# SCH_SlimeVR_Charge_HUB_2022-04-14.net
KiCad netlist of a schematic drawn in EasyEDA
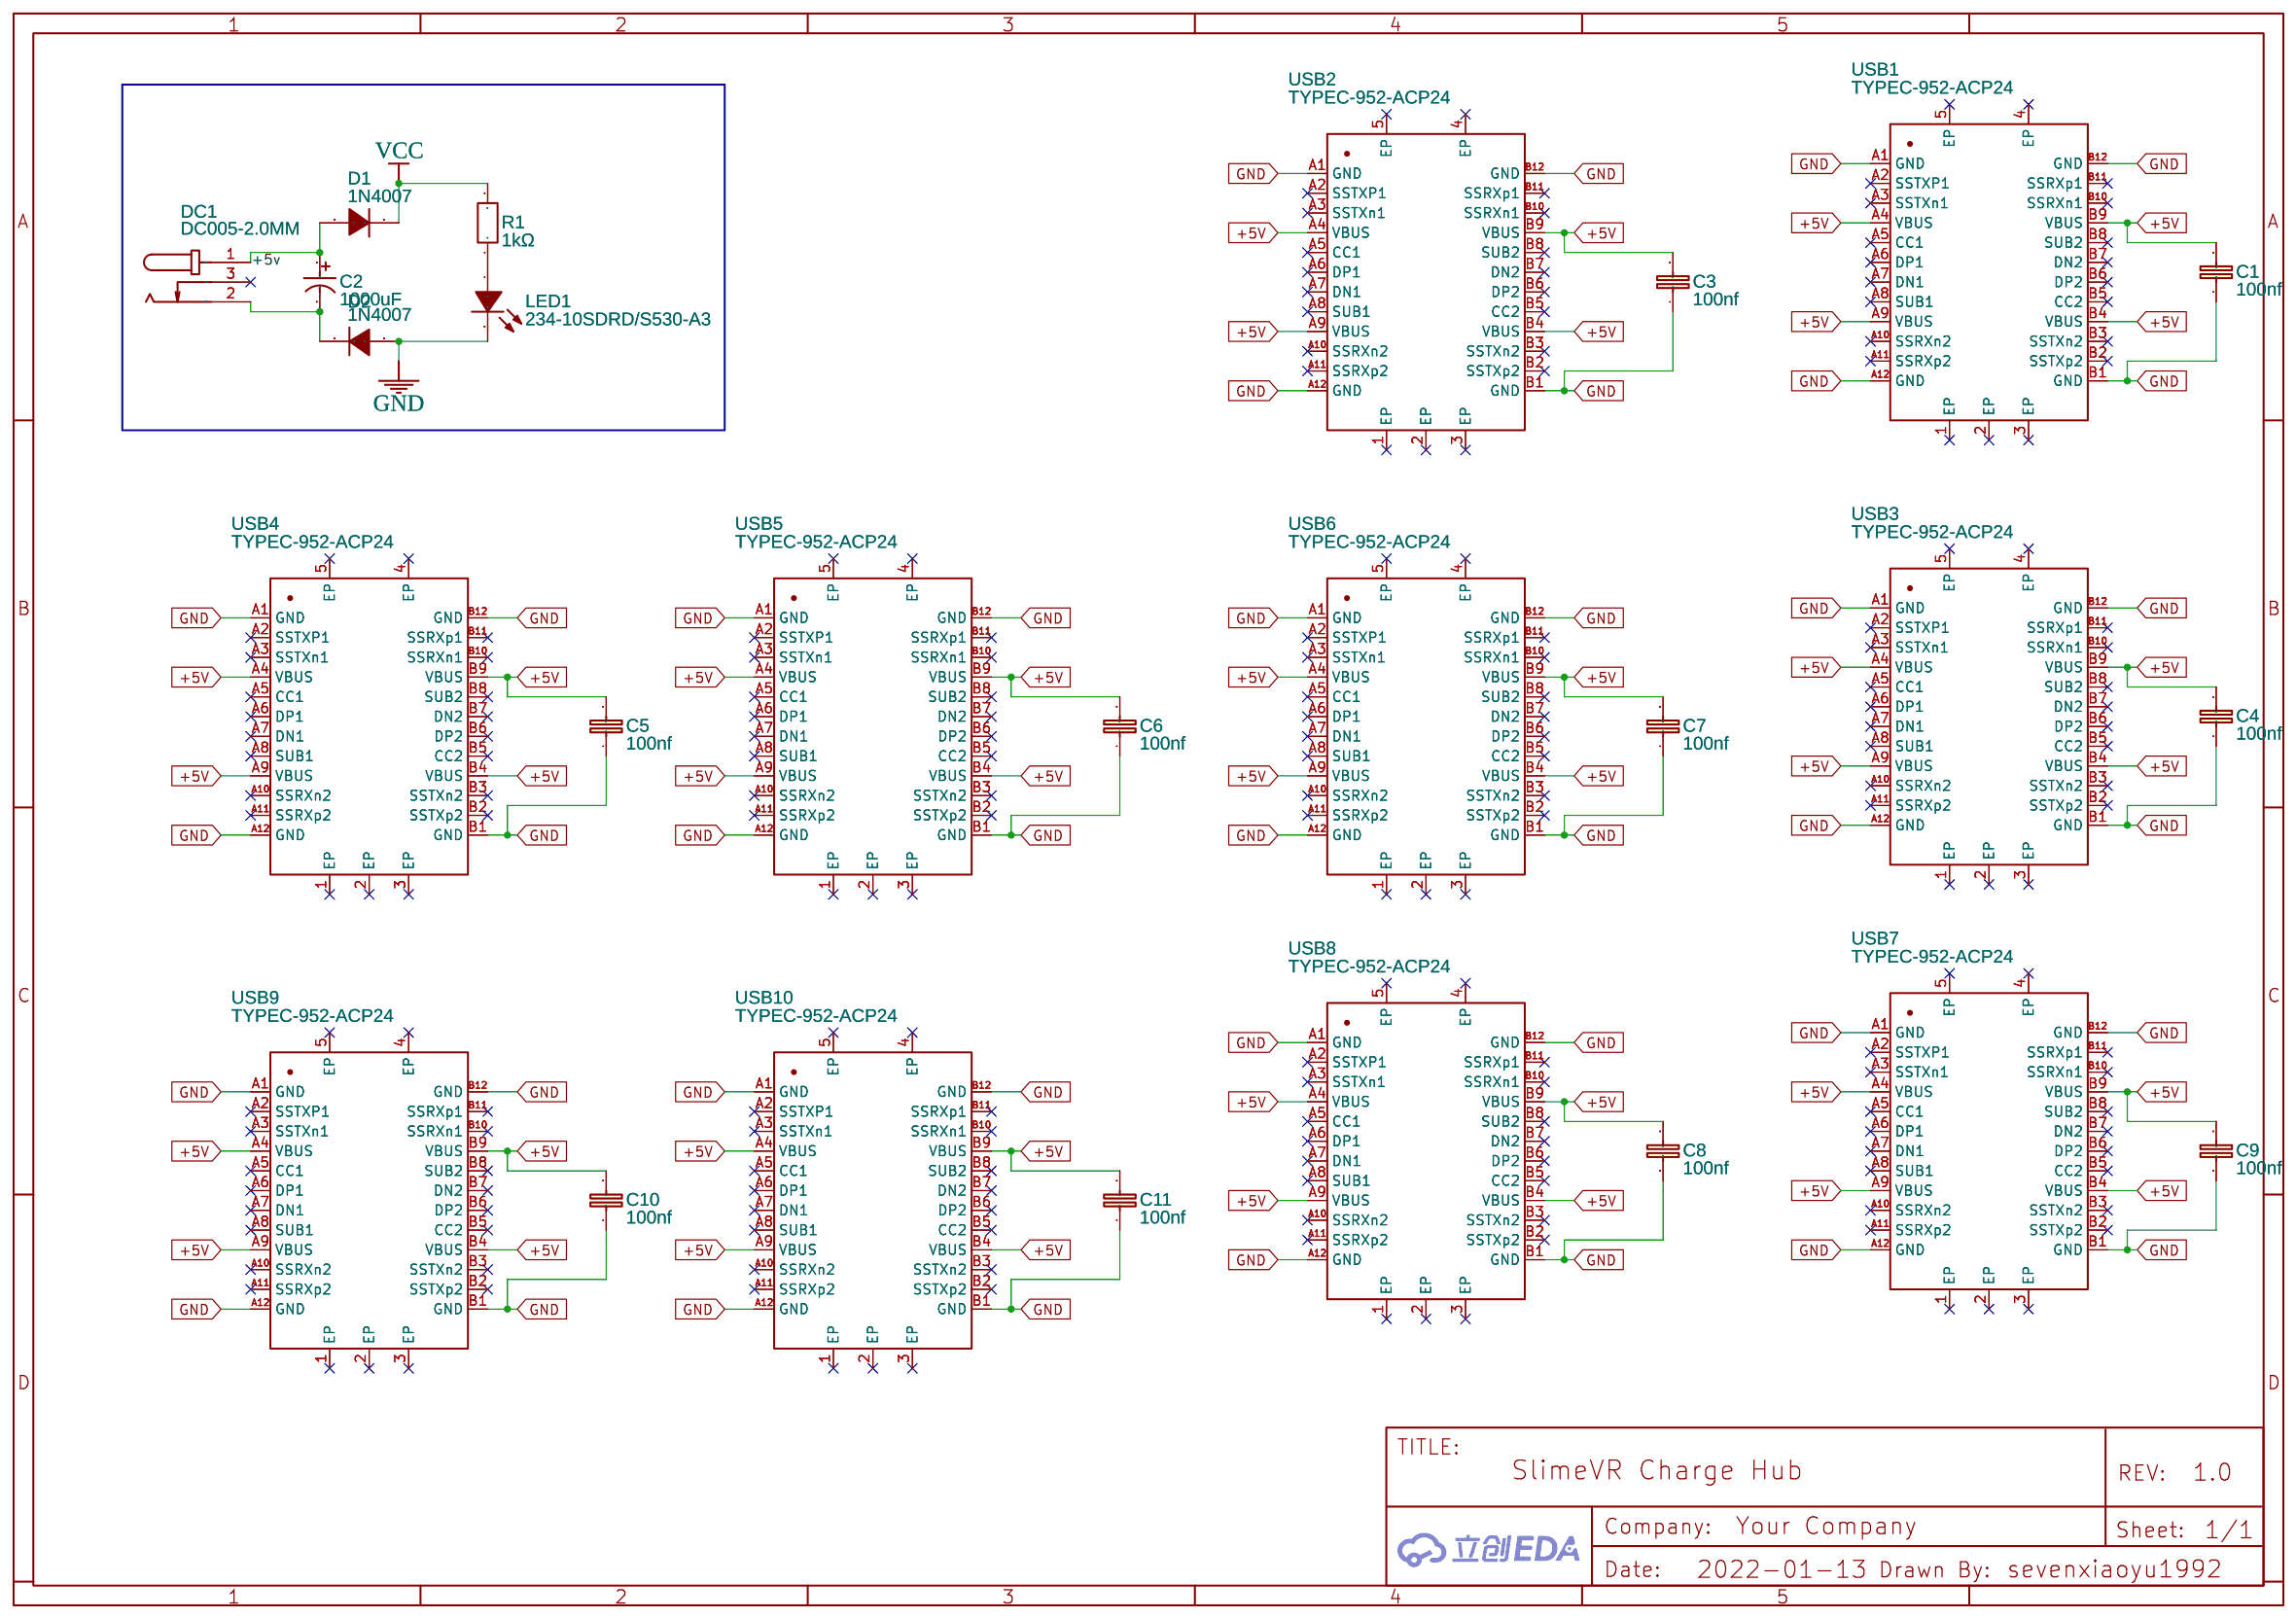
[diagram p0: schematic sheet]

(export (version "E")
  (design (tool "Eeschema 10.0.6"))
  (components
    (comp (ref "C1")
      (value "100nf")
      (fields (field (name "BOM_Manufacturer Part") "?"))
      (libsource (lib "") (part "Unknown_1115_-675"))
    )
    (comp (ref "C2")
      (value "1000uF")
      (fields
        (field (name "BOM_Manufacturer Part") "1000uF 10V绿金 10*15")
        (field (name "BOM_Supplier Part") "C43339")
      )
      (libsource (lib "") (part "1000uF 10V 10*15"))
    )
    (comp (ref "C3")
      (value "100nf")
      (fields (field (name "BOM_Manufacturer Part") "?"))
      (libsource (lib "") (part "Unknown_840_-670"))
    )
    (comp (ref "C4")
      (value "100nf")
      (fields (field (name "BOM_Manufacturer Part") "?"))
      (libsource (lib "") (part "Unknown_1115_-450"))
    )
    (comp (ref "C5")
      (value "100nf")
      (fields (field (name "BOM_Manufacturer Part") "?"))
      (libsource (lib "") (part "Unknown_300_-445"))
    )
    (comp (ref "C6")
      (value "100nf")
      (fields (field (name "BOM_Manufacturer Part") "?"))
      (libsource (lib "") (part "Unknown_560_-445"))
    )
    (comp (ref "C7")
      (value "100nf")
      (fields (field (name "BOM_Manufacturer Part") "?"))
      (libsource (lib "") (part "Unknown_835_-445"))
    )
    (comp (ref "C8")
      (value "100nf")
      (fields (field (name "BOM_Manufacturer Part") "?"))
      (libsource (lib "") (part "Unknown_835_-230"))
    )
    (comp (ref "C9")
      (value "100nf")
      (fields (field (name "BOM_Manufacturer Part") "?"))
      (libsource (lib "") (part "Unknown_1115_-230"))
    )
    (comp (ref "C10")
      (value "100nf")
      (fields (field (name "BOM_Manufacturer Part") "?"))
      (libsource (lib "") (part "Unknown_300_-205"))
    )
    (comp (ref "C11")
      (value "100nf")
      (fields (field (name "BOM_Manufacturer Part") "?"))
      (libsource (lib "") (part "Unknown_560_-205"))
    )
    (comp (ref "D1")
      (value "1N4007")
      (fields (field (name "BOM_Supplier Part") "C106903"))
      (libsource (lib "") (part "1N4007"))
    )
    (comp (ref "D2")
      (value "1N4007")
      (fields (field (name "BOM_Supplier Part") "C106903"))
      (libsource (lib "") (part "1N4007_1"))
    )
    (comp (ref "DC1")
      (value "DC005-2.0MM")
      (fields (field (name "BOM_Supplier Part") "C111567"))
      (libsource (lib "") (part "DC005-2.0MM"))
    )
    (comp (ref "LED1")
      (value "234-10SDRD/S530-A3")
      (fields (field (name "BOM_Supplier Part") "C181866"))
      (libsource (lib "") (part "234-10SDRD/S530-A3"))
    )
    (comp (ref "R1")
      (value "1kΩ")
      (fields
        (field (name "BOM_Manufacturer Part") "MF1/2W-1KΩ±1%T52")
        (field (name "BOM_Supplier Part") "C714068")
      )
      (libsource (lib "") (part "MF1/2W-1KΩ±1%T52"))
    )
    (comp (ref "USB1")
      (value "TYPEC-952-ACP24")
      (fields (field (name "BOM_Supplier Part") "C2840398"))
      (libsource (lib "") (part "TYPEC-952-ACP24"))
    )
    (comp (ref "USB2")
      (value "TYPEC-952-ACP24")
      (fields (field (name "BOM_Supplier Part") "C2840398"))
      (libsource (lib "") (part "TYPEC-952-ACP24"))
    )
    (comp (ref "USB3")
      (value "TYPEC-952-ACP24")
      (fields (field (name "BOM_Supplier Part") "C2840398"))
      (libsource (lib "") (part "TYPEC-952-ACP24"))
    )
    (comp (ref "USB4")
      (value "TYPEC-952-ACP24")
      (fields (field (name "BOM_Supplier Part") "C2840398"))
      (libsource (lib "") (part "TYPEC-952-ACP24"))
    )
    (comp (ref "USB5")
      (value "TYPEC-952-ACP24")
      (fields (field (name "BOM_Supplier Part") "C2840398"))
      (libsource (lib "") (part "TYPEC-952-ACP24"))
    )
    (comp (ref "USB6")
      (value "TYPEC-952-ACP24")
      (fields (field (name "BOM_Supplier Part") "C2840398"))
      (libsource (lib "") (part "TYPEC-952-ACP24"))
    )
    (comp (ref "USB7")
      (value "TYPEC-952-ACP24")
      (fields (field (name "BOM_Supplier Part") "C2840398"))
      (libsource (lib "") (part "TYPEC-952-ACP24"))
    )
    (comp (ref "USB8")
      (value "TYPEC-952-ACP24")
      (fields (field (name "BOM_Supplier Part") "C2840398"))
      (libsource (lib "") (part "TYPEC-952-ACP24"))
    )
    (comp (ref "USB9")
      (value "TYPEC-952-ACP24")
      (fields (field (name "BOM_Supplier Part") "C2840398"))
      (libsource (lib "") (part "TYPEC-952-ACP24"))
    )
    (comp (ref "USB10")
      (value "TYPEC-952-ACP24")
      (fields (field (name "BOM_Supplier Part") "C2840398"))
      (libsource (lib "") (part "TYPEC-952-ACP24"))
    )
  )
  (nets
    (net (code "1") (name "+5V") (class "Default")
      (node (ref "C1") (pin "2") (pinfunction "2_2") (pintype "unspecified"))
      (node (ref "C10") (pin "2") (pinfunction "2_2") (pintype "unspecified"))
      (node (ref "C11") (pin "2") (pinfunction "2_2") (pintype "unspecified"))
      (node (ref "C3") (pin "2") (pinfunction "2_2") (pintype "unspecified"))
      (node (ref "C4") (pin "2") (pinfunction "2_2") (pintype "unspecified"))
      (node (ref "C5") (pin "2") (pinfunction "2_2") (pintype "unspecified"))
      (node (ref "C6") (pin "2") (pinfunction "2_2") (pintype "unspecified"))
      (node (ref "C7") (pin "2") (pinfunction "2_2") (pintype "unspecified"))
      (node (ref "C8") (pin "2") (pinfunction "2_2") (pintype "unspecified"))
      (node (ref "C9") (pin "2") (pinfunction "2_2") (pintype "unspecified"))
      (node (ref "USB1") (pin "A4") (pinfunction "VBUS_A4") (pintype "unspecified"))
      (node (ref "USB1") (pin "A9") (pinfunction "VBUS_A9") (pintype "unspecified"))
      (node (ref "USB1") (pin "B4") (pinfunction "VBUS_B4") (pintype "unspecified"))
      (node (ref "USB1") (pin "B9") (pinfunction "VBUS_B9") (pintype "unspecified"))
      (node (ref "USB10") (pin "A4") (pinfunction "VBUS_A4") (pintype "unspecified"))
      (node (ref "USB10") (pin "A9") (pinfunction "VBUS_A9") (pintype "unspecified"))
      (node (ref "USB10") (pin "B4") (pinfunction "VBUS_B4") (pintype "unspecified"))
      (node (ref "USB10") (pin "B9") (pinfunction "VBUS_B9") (pintype "unspecified"))
      (node (ref "USB2") (pin "A4") (pinfunction "VBUS_A4") (pintype "unspecified"))
      (node (ref "USB2") (pin "A9") (pinfunction "VBUS_A9") (pintype "unspecified"))
      (node (ref "USB2") (pin "B4") (pinfunction "VBUS_B4") (pintype "unspecified"))
      (node (ref "USB2") (pin "B9") (pinfunction "VBUS_B9") (pintype "unspecified"))
      (node (ref "USB3") (pin "A4") (pinfunction "VBUS_A4") (pintype "unspecified"))
      (node (ref "USB3") (pin "A9") (pinfunction "VBUS_A9") (pintype "unspecified"))
      (node (ref "USB3") (pin "B4") (pinfunction "VBUS_B4") (pintype "unspecified"))
      (node (ref "USB3") (pin "B9") (pinfunction "VBUS_B9") (pintype "unspecified"))
      (node (ref "USB4") (pin "A4") (pinfunction "VBUS_A4") (pintype "unspecified"))
      (node (ref "USB4") (pin "A9") (pinfunction "VBUS_A9") (pintype "unspecified"))
      (node (ref "USB4") (pin "B4") (pinfunction "VBUS_B4") (pintype "unspecified"))
      (node (ref "USB4") (pin "B9") (pinfunction "VBUS_B9") (pintype "unspecified"))
      (node (ref "USB5") (pin "A4") (pinfunction "VBUS_A4") (pintype "unspecified"))
      (node (ref "USB5") (pin "A9") (pinfunction "VBUS_A9") (pintype "unspecified"))
      (node (ref "USB5") (pin "B4") (pinfunction "VBUS_B4") (pintype "unspecified"))
      (node (ref "USB5") (pin "B9") (pinfunction "VBUS_B9") (pintype "unspecified"))
      (node (ref "USB6") (pin "A4") (pinfunction "VBUS_A4") (pintype "unspecified"))
      (node (ref "USB6") (pin "A9") (pinfunction "VBUS_A9") (pintype "unspecified"))
      (node (ref "USB6") (pin "B4") (pinfunction "VBUS_B4") (pintype "unspecified"))
      (node (ref "USB6") (pin "B9") (pinfunction "VBUS_B9") (pintype "unspecified"))
      (node (ref "USB7") (pin "A4") (pinfunction "VBUS_A4") (pintype "unspecified"))
      (node (ref "USB7") (pin "A9") (pinfunction "VBUS_A9") (pintype "unspecified"))
      (node (ref "USB7") (pin "B4") (pinfunction "VBUS_B4") (pintype "unspecified"))
      (node (ref "USB7") (pin "B9") (pinfunction "VBUS_B9") (pintype "unspecified"))
      (node (ref "USB8") (pin "A4") (pinfunction "VBUS_A4") (pintype "unspecified"))
      (node (ref "USB8") (pin "A9") (pinfunction "VBUS_A9") (pintype "unspecified"))
      (node (ref "USB8") (pin "B4") (pinfunction "VBUS_B4") (pintype "unspecified"))
      (node (ref "USB8") (pin "B9") (pinfunction "VBUS_B9") (pintype "unspecified"))
      (node (ref "USB9") (pin "A4") (pinfunction "VBUS_A4") (pintype "unspecified"))
      (node (ref "USB9") (pin "A9") (pinfunction "VBUS_A9") (pintype "unspecified"))
      (node (ref "USB9") (pin "B4") (pinfunction "VBUS_B4") (pintype "unspecified"))
      (node (ref "USB9") (pin "B9") (pinfunction "VBUS_B9") (pintype "unspecified"))
    )
    (net (code "2") (name "/+5v") (class "Default")
      (node (ref "C2") (pin "1") (pinfunction "1_1") (pintype "input"))
      (node (ref "D1") (pin "2") (pinfunction "A_2") (pintype "unspecified"))
      (node (ref "DC1") (pin "1") (pinfunction "1_1") (pintype "unspecified"))
    )
    (net (code "3") (name "GND") (class "Default")
      (node (ref "C1") (pin "1") (pinfunction "1_1") (pintype "unspecified"))
      (node (ref "C10") (pin "1") (pinfunction "1_1") (pintype "unspecified"))
      (node (ref "C11") (pin "1") (pinfunction "1_1") (pintype "unspecified"))
      (node (ref "C3") (pin "1") (pinfunction "1_1") (pintype "unspecified"))
      (node (ref "C4") (pin "1") (pinfunction "1_1") (pintype "unspecified"))
      (node (ref "C5") (pin "1") (pinfunction "1_1") (pintype "unspecified"))
      (node (ref "C6") (pin "1") (pinfunction "1_1") (pintype "unspecified"))
      (node (ref "C7") (pin "1") (pinfunction "1_1") (pintype "unspecified"))
      (node (ref "C8") (pin "1") (pinfunction "1_1") (pintype "unspecified"))
      (node (ref "C9") (pin "1") (pinfunction "1_1") (pintype "unspecified"))
      (node (ref "D2") (pin "2") (pinfunction "A_2") (pintype "unspecified"))
      (node (ref "LED1") (pin "2") (pinfunction "K_2") (pintype "unspecified"))
      (node (ref "USB1") (pin "A1") (pinfunction "GND_A1") (pintype "unspecified"))
      (node (ref "USB1") (pin "A12") (pinfunction "GND_A12") (pintype "unspecified"))
      (node (ref "USB1") (pin "B1") (pinfunction "GND_B1") (pintype "unspecified"))
      (node (ref "USB1") (pin "B12") (pinfunction "GND_B12") (pintype "unspecified"))
      (node (ref "USB10") (pin "A1") (pinfunction "GND_A1") (pintype "unspecified"))
      (node (ref "USB10") (pin "A12") (pinfunction "GND_A12") (pintype "unspecified"))
      (node (ref "USB10") (pin "B1") (pinfunction "GND_B1") (pintype "unspecified"))
      (node (ref "USB10") (pin "B12") (pinfunction "GND_B12") (pintype "unspecified"))
      (node (ref "USB2") (pin "A1") (pinfunction "GND_A1") (pintype "unspecified"))
      (node (ref "USB2") (pin "A12") (pinfunction "GND_A12") (pintype "unspecified"))
      (node (ref "USB2") (pin "B1") (pinfunction "GND_B1") (pintype "unspecified"))
      (node (ref "USB2") (pin "B12") (pinfunction "GND_B12") (pintype "unspecified"))
      (node (ref "USB3") (pin "A1") (pinfunction "GND_A1") (pintype "unspecified"))
      (node (ref "USB3") (pin "A12") (pinfunction "GND_A12") (pintype "unspecified"))
      (node (ref "USB3") (pin "B1") (pinfunction "GND_B1") (pintype "unspecified"))
      (node (ref "USB3") (pin "B12") (pinfunction "GND_B12") (pintype "unspecified"))
      (node (ref "USB4") (pin "A1") (pinfunction "GND_A1") (pintype "unspecified"))
      (node (ref "USB4") (pin "A12") (pinfunction "GND_A12") (pintype "unspecified"))
      (node (ref "USB4") (pin "B1") (pinfunction "GND_B1") (pintype "unspecified"))
      (node (ref "USB4") (pin "B12") (pinfunction "GND_B12") (pintype "unspecified"))
      (node (ref "USB5") (pin "A1") (pinfunction "GND_A1") (pintype "unspecified"))
      (node (ref "USB5") (pin "A12") (pinfunction "GND_A12") (pintype "unspecified"))
      (node (ref "USB5") (pin "B1") (pinfunction "GND_B1") (pintype "unspecified"))
      (node (ref "USB5") (pin "B12") (pinfunction "GND_B12") (pintype "unspecified"))
      (node (ref "USB6") (pin "A1") (pinfunction "GND_A1") (pintype "unspecified"))
      (node (ref "USB6") (pin "A12") (pinfunction "GND_A12") (pintype "unspecified"))
      (node (ref "USB6") (pin "B1") (pinfunction "GND_B1") (pintype "unspecified"))
      (node (ref "USB6") (pin "B12") (pinfunction "GND_B12") (pintype "unspecified"))
      (node (ref "USB7") (pin "A1") (pinfunction "GND_A1") (pintype "unspecified"))
      (node (ref "USB7") (pin "A12") (pinfunction "GND_A12") (pintype "unspecified"))
      (node (ref "USB7") (pin "B1") (pinfunction "GND_B1") (pintype "unspecified"))
      (node (ref "USB7") (pin "B12") (pinfunction "GND_B12") (pintype "unspecified"))
      (node (ref "USB8") (pin "A1") (pinfunction "GND_A1") (pintype "unspecified"))
      (node (ref "USB8") (pin "A12") (pinfunction "GND_A12") (pintype "unspecified"))
      (node (ref "USB8") (pin "B1") (pinfunction "GND_B1") (pintype "unspecified"))
      (node (ref "USB8") (pin "B12") (pinfunction "GND_B12") (pintype "unspecified"))
      (node (ref "USB9") (pin "A1") (pinfunction "GND_A1") (pintype "unspecified"))
      (node (ref "USB9") (pin "A12") (pinfunction "GND_A12") (pintype "unspecified"))
      (node (ref "USB9") (pin "B1") (pinfunction "GND_B1") (pintype "unspecified"))
      (node (ref "USB9") (pin "B12") (pinfunction "GND_B12") (pintype "unspecified"))
    )
    (net (code "4") (name "Net-(D2-K)") (class "Default")
      (node (ref "C2") (pin "2") (pinfunction "2_2") (pintype "input"))
      (node (ref "D2") (pin "1") (pinfunction "K_1") (pintype "unspecified"))
      (node (ref "DC1") (pin "2") (pinfunction "2_2") (pintype "unspecified"))
    )
    (net (code "5") (name "Net-(LED1-A)") (class "Default")
      (node (ref "LED1") (pin "1") (pinfunction "A_1") (pintype "unspecified"))
      (node (ref "R1") (pin "1") (pinfunction "1_1") (pintype "unspecified"))
    )
    (net (code "6") (name "VCC") (class "Default")
      (node (ref "D1") (pin "1") (pinfunction "K_1") (pintype "unspecified"))
      (node (ref "R1") (pin "2") (pinfunction "2_2") (pintype "unspecified"))
    )
    (net (code "7") (name "unconnected-(DC1-Pad3)") (class "Default")
      (node (ref "DC1") (pin "3") (pinfunction "3_3") (pintype "unspecified+no_connect"))
    )
    (net (code "8") (name "unconnected-(USB1-CC1-PadA5)") (class "Default")
      (node (ref "USB1") (pin "A5") (pinfunction "CC1_A5") (pintype "unspecified+no_connect"))
    )
    (net (code "9") (name "unconnected-(USB1-CC2-PadB5)") (class "Default")
      (node (ref "USB1") (pin "B5") (pinfunction "CC2_B5") (pintype "unspecified+no_connect"))
    )
    (net (code "10") (name "unconnected-(USB1-DN1-PadA7)") (class "Default")
      (node (ref "USB1") (pin "A7") (pinfunction "DN1_A7") (pintype "unspecified+no_connect"))
    )
    (net (code "11") (name "unconnected-(USB1-DN2-PadB7)") (class "Default")
      (node (ref "USB1") (pin "B7") (pinfunction "DN2_B7") (pintype "unspecified+no_connect"))
    )
    (net (code "12") (name "unconnected-(USB1-DP1-PadA6)") (class "Default")
      (node (ref "USB1") (pin "A6") (pinfunction "DP1_A6") (pintype "unspecified+no_connect"))
    )
    (net (code "13") (name "unconnected-(USB1-DP2-PadB6)") (class "Default")
      (node (ref "USB1") (pin "B6") (pinfunction "DP2_B6") (pintype "unspecified+no_connect"))
    )
    (net (code "14") (name "unconnected-(USB1-EP-Pad1)") (class "Default")
      (node (ref "USB1") (pin "1") (pinfunction "EP_1") (pintype "unspecified+no_connect"))
    )
    (net (code "15") (name "unconnected-(USB1-EP-Pad2)") (class "Default")
      (node (ref "USB1") (pin "2") (pinfunction "EP_2") (pintype "unspecified+no_connect"))
    )
    (net (code "16") (name "unconnected-(USB1-EP-Pad3)") (class "Default")
      (node (ref "USB1") (pin "3") (pinfunction "EP_3") (pintype "unspecified+no_connect"))
    )
    (net (code "17") (name "unconnected-(USB1-EP-Pad4)") (class "Default")
      (node (ref "USB1") (pin "4") (pinfunction "EP_4") (pintype "unspecified+no_connect"))
    )
    (net (code "18") (name "unconnected-(USB1-EP-Pad5)") (class "Default")
      (node (ref "USB1") (pin "5") (pinfunction "EP_5") (pintype "unspecified+no_connect"))
    )
    (net (code "19") (name "unconnected-(USB1-SSRXn1-PadB10)") (class "Default")
      (node (ref "USB1") (pin "B10") (pinfunction "SSRXn1_B10") (pintype "unspecified+no_connect"))
    )
    (net (code "20") (name "unconnected-(USB1-SSRXn2-PadA10)") (class "Default")
      (node (ref "USB1") (pin "A10") (pinfunction "SSRXn2_A10") (pintype "unspecified+no_connect"))
    )
    (net (code "21") (name "unconnected-(USB1-SSRXp1-PadB11)") (class "Default")
      (node (ref "USB1") (pin "B11") (pinfunction "SSRXp1_B11") (pintype "unspecified+no_connect"))
    )
    (net (code "22") (name "unconnected-(USB1-SSRXp2-PadA11)") (class "Default")
      (node (ref "USB1") (pin "A11") (pinfunction "SSRXp2_A11") (pintype "unspecified+no_connect"))
    )
    (net (code "23") (name "unconnected-(USB1-SSTXP1-PadA2)") (class "Default")
      (node (ref "USB1") (pin "A2") (pinfunction "SSTXP1_A2") (pintype "unspecified+no_connect"))
    )
    (net (code "24") (name "unconnected-(USB1-SSTXn1-PadA3)") (class "Default")
      (node (ref "USB1") (pin "A3") (pinfunction "SSTXn1_A3") (pintype "unspecified+no_connect"))
    )
    (net (code "25") (name "unconnected-(USB1-SSTXn2-PadB3)") (class "Default")
      (node (ref "USB1") (pin "B3") (pinfunction "SSTXn2_B3") (pintype "unspecified+no_connect"))
    )
    (net (code "26") (name "unconnected-(USB1-SSTXp2-PadB2)") (class "Default")
      (node (ref "USB1") (pin "B2") (pinfunction "SSTXp2_B2") (pintype "unspecified+no_connect"))
    )
    (net (code "27") (name "unconnected-(USB1-SUB1-PadA8)") (class "Default")
      (node (ref "USB1") (pin "A8") (pinfunction "SUB1_A8") (pintype "unspecified+no_connect"))
    )
    (net (code "28") (name "unconnected-(USB1-SUB2-PadB8)") (class "Default")
      (node (ref "USB1") (pin "B8") (pinfunction "SUB2_B8") (pintype "unspecified+no_connect"))
    )
    (net (code "29") (name "unconnected-(USB2-CC1-PadA5)") (class "Default")
      (node (ref "USB2") (pin "A5") (pinfunction "CC1_A5") (pintype "unspecified+no_connect"))
    )
    (net (code "30") (name "unconnected-(USB2-CC2-PadB5)") (class "Default")
      (node (ref "USB2") (pin "B5") (pinfunction "CC2_B5") (pintype "unspecified+no_connect"))
    )
    (net (code "31") (name "unconnected-(USB2-DN1-PadA7)") (class "Default")
      (node (ref "USB2") (pin "A7") (pinfunction "DN1_A7") (pintype "unspecified+no_connect"))
    )
    (net (code "32") (name "unconnected-(USB2-DN2-PadB7)") (class "Default")
      (node (ref "USB2") (pin "B7") (pinfunction "DN2_B7") (pintype "unspecified+no_connect"))
    )
    (net (code "33") (name "unconnected-(USB2-DP1-PadA6)") (class "Default")
      (node (ref "USB2") (pin "A6") (pinfunction "DP1_A6") (pintype "unspecified+no_connect"))
    )
    (net (code "34") (name "unconnected-(USB2-DP2-PadB6)") (class "Default")
      (node (ref "USB2") (pin "B6") (pinfunction "DP2_B6") (pintype "unspecified+no_connect"))
    )
    (net (code "35") (name "unconnected-(USB2-EP-Pad1)") (class "Default")
      (node (ref "USB2") (pin "1") (pinfunction "EP_1") (pintype "unspecified+no_connect"))
    )
    (net (code "36") (name "unconnected-(USB2-EP-Pad2)") (class "Default")
      (node (ref "USB2") (pin "2") (pinfunction "EP_2") (pintype "unspecified+no_connect"))
    )
    (net (code "37") (name "unconnected-(USB2-EP-Pad3)") (class "Default")
      (node (ref "USB2") (pin "3") (pinfunction "EP_3") (pintype "unspecified+no_connect"))
    )
    (net (code "38") (name "unconnected-(USB2-EP-Pad4)") (class "Default")
      (node (ref "USB2") (pin "4") (pinfunction "EP_4") (pintype "unspecified+no_connect"))
    )
    (net (code "39") (name "unconnected-(USB2-EP-Pad5)") (class "Default")
      (node (ref "USB2") (pin "5") (pinfunction "EP_5") (pintype "unspecified+no_connect"))
    )
    (net (code "40") (name "unconnected-(USB2-SSRXn1-PadB10)") (class "Default")
      (node (ref "USB2") (pin "B10") (pinfunction "SSRXn1_B10") (pintype "unspecified+no_connect"))
    )
    (net (code "41") (name "unconnected-(USB2-SSRXn2-PadA10)") (class "Default")
      (node (ref "USB2") (pin "A10") (pinfunction "SSRXn2_A10") (pintype "unspecified+no_connect"))
    )
    (net (code "42") (name "unconnected-(USB2-SSRXp1-PadB11)") (class "Default")
      (node (ref "USB2") (pin "B11") (pinfunction "SSRXp1_B11") (pintype "unspecified+no_connect"))
    )
    (net (code "43") (name "unconnected-(USB2-SSRXp2-PadA11)") (class "Default")
      (node (ref "USB2") (pin "A11") (pinfunction "SSRXp2_A11") (pintype "unspecified+no_connect"))
    )
    (net (code "44") (name "unconnected-(USB2-SSTXP1-PadA2)") (class "Default")
      (node (ref "USB2") (pin "A2") (pinfunction "SSTXP1_A2") (pintype "unspecified+no_connect"))
    )
    (net (code "45") (name "unconnected-(USB2-SSTXn1-PadA3)") (class "Default")
      (node (ref "USB2") (pin "A3") (pinfunction "SSTXn1_A3") (pintype "unspecified+no_connect"))
    )
    (net (code "46") (name "unconnected-(USB2-SSTXn2-PadB3)") (class "Default")
      (node (ref "USB2") (pin "B3") (pinfunction "SSTXn2_B3") (pintype "unspecified+no_connect"))
    )
    (net (code "47") (name "unconnected-(USB2-SSTXp2-PadB2)") (class "Default")
      (node (ref "USB2") (pin "B2") (pinfunction "SSTXp2_B2") (pintype "unspecified+no_connect"))
    )
    (net (code "48") (name "unconnected-(USB2-SUB1-PadA8)") (class "Default")
      (node (ref "USB2") (pin "A8") (pinfunction "SUB1_A8") (pintype "unspecified+no_connect"))
    )
    (net (code "49") (name "unconnected-(USB2-SUB2-PadB8)") (class "Default")
      (node (ref "USB2") (pin "B8") (pinfunction "SUB2_B8") (pintype "unspecified+no_connect"))
    )
    (net (code "50") (name "unconnected-(USB3-CC1-PadA5)") (class "Default")
      (node (ref "USB3") (pin "A5") (pinfunction "CC1_A5") (pintype "unspecified+no_connect"))
    )
    (net (code "51") (name "unconnected-(USB3-CC2-PadB5)") (class "Default")
      (node (ref "USB3") (pin "B5") (pinfunction "CC2_B5") (pintype "unspecified+no_connect"))
    )
    (net (code "52") (name "unconnected-(USB3-DN1-PadA7)") (class "Default")
      (node (ref "USB3") (pin "A7") (pinfunction "DN1_A7") (pintype "unspecified+no_connect"))
    )
    (net (code "53") (name "unconnected-(USB3-DN2-PadB7)") (class "Default")
      (node (ref "USB3") (pin "B7") (pinfunction "DN2_B7") (pintype "unspecified+no_connect"))
    )
    (net (code "54") (name "unconnected-(USB3-DP1-PadA6)") (class "Default")
      (node (ref "USB3") (pin "A6") (pinfunction "DP1_A6") (pintype "unspecified+no_connect"))
    )
    (net (code "55") (name "unconnected-(USB3-DP2-PadB6)") (class "Default")
      (node (ref "USB3") (pin "B6") (pinfunction "DP2_B6") (pintype "unspecified+no_connect"))
    )
    (net (code "56") (name "unconnected-(USB3-EP-Pad1)") (class "Default")
      (node (ref "USB3") (pin "1") (pinfunction "EP_1") (pintype "unspecified+no_connect"))
    )
    (net (code "57") (name "unconnected-(USB3-EP-Pad2)") (class "Default")
      (node (ref "USB3") (pin "2") (pinfunction "EP_2") (pintype "unspecified+no_connect"))
    )
    (net (code "58") (name "unconnected-(USB3-EP-Pad3)") (class "Default")
      (node (ref "USB3") (pin "3") (pinfunction "EP_3") (pintype "unspecified+no_connect"))
    )
    (net (code "59") (name "unconnected-(USB3-EP-Pad4)") (class "Default")
      (node (ref "USB3") (pin "4") (pinfunction "EP_4") (pintype "unspecified+no_connect"))
    )
    (net (code "60") (name "unconnected-(USB3-EP-Pad5)") (class "Default")
      (node (ref "USB3") (pin "5") (pinfunction "EP_5") (pintype "unspecified+no_connect"))
    )
    (net (code "61") (name "unconnected-(USB3-SSRXn1-PadB10)") (class "Default")
      (node (ref "USB3") (pin "B10") (pinfunction "SSRXn1_B10") (pintype "unspecified+no_connect"))
    )
    (net (code "62") (name "unconnected-(USB3-SSRXn2-PadA10)") (class "Default")
      (node (ref "USB3") (pin "A10") (pinfunction "SSRXn2_A10") (pintype "unspecified+no_connect"))
    )
    (net (code "63") (name "unconnected-(USB3-SSRXp1-PadB11)") (class "Default")
      (node (ref "USB3") (pin "B11") (pinfunction "SSRXp1_B11") (pintype "unspecified+no_connect"))
    )
    (net (code "64") (name "unconnected-(USB3-SSRXp2-PadA11)") (class "Default")
      (node (ref "USB3") (pin "A11") (pinfunction "SSRXp2_A11") (pintype "unspecified+no_connect"))
    )
    (net (code "65") (name "unconnected-(USB3-SSTXP1-PadA2)") (class "Default")
      (node (ref "USB3") (pin "A2") (pinfunction "SSTXP1_A2") (pintype "unspecified+no_connect"))
    )
    (net (code "66") (name "unconnected-(USB3-SSTXn1-PadA3)") (class "Default")
      (node (ref "USB3") (pin "A3") (pinfunction "SSTXn1_A3") (pintype "unspecified+no_connect"))
    )
    (net (code "67") (name "unconnected-(USB3-SSTXn2-PadB3)") (class "Default")
      (node (ref "USB3") (pin "B3") (pinfunction "SSTXn2_B3") (pintype "unspecified+no_connect"))
    )
    (net (code "68") (name "unconnected-(USB3-SSTXp2-PadB2)") (class "Default")
      (node (ref "USB3") (pin "B2") (pinfunction "SSTXp2_B2") (pintype "unspecified+no_connect"))
    )
    (net (code "69") (name "unconnected-(USB3-SUB1-PadA8)") (class "Default")
      (node (ref "USB3") (pin "A8") (pinfunction "SUB1_A8") (pintype "unspecified+no_connect"))
    )
    (net (code "70") (name "unconnected-(USB3-SUB2-PadB8)") (class "Default")
      (node (ref "USB3") (pin "B8") (pinfunction "SUB2_B8") (pintype "unspecified+no_connect"))
    )
    (net (code "71") (name "unconnected-(USB4-CC1-PadA5)") (class "Default")
      (node (ref "USB4") (pin "A5") (pinfunction "CC1_A5") (pintype "unspecified+no_connect"))
    )
    (net (code "72") (name "unconnected-(USB4-CC2-PadB5)") (class "Default")
      (node (ref "USB4") (pin "B5") (pinfunction "CC2_B5") (pintype "unspecified+no_connect"))
    )
    (net (code "73") (name "unconnected-(USB4-DN1-PadA7)") (class "Default")
      (node (ref "USB4") (pin "A7") (pinfunction "DN1_A7") (pintype "unspecified+no_connect"))
    )
    (net (code "74") (name "unconnected-(USB4-DN2-PadB7)") (class "Default")
      (node (ref "USB4") (pin "B7") (pinfunction "DN2_B7") (pintype "unspecified+no_connect"))
    )
    (net (code "75") (name "unconnected-(USB4-DP1-PadA6)") (class "Default")
      (node (ref "USB4") (pin "A6") (pinfunction "DP1_A6") (pintype "unspecified+no_connect"))
    )
    (net (code "76") (name "unconnected-(USB4-DP2-PadB6)") (class "Default")
      (node (ref "USB4") (pin "B6") (pinfunction "DP2_B6") (pintype "unspecified+no_connect"))
    )
    (net (code "77") (name "unconnected-(USB4-EP-Pad1)") (class "Default")
      (node (ref "USB4") (pin "1") (pinfunction "EP_1") (pintype "unspecified+no_connect"))
    )
    (net (code "78") (name "unconnected-(USB4-EP-Pad2)") (class "Default")
      (node (ref "USB4") (pin "2") (pinfunction "EP_2") (pintype "unspecified+no_connect"))
    )
    (net (code "79") (name "unconnected-(USB4-EP-Pad3)") (class "Default")
      (node (ref "USB4") (pin "3") (pinfunction "EP_3") (pintype "unspecified+no_connect"))
    )
    (net (code "80") (name "unconnected-(USB4-EP-Pad4)") (class "Default")
      (node (ref "USB4") (pin "4") (pinfunction "EP_4") (pintype "unspecified+no_connect"))
    )
    (net (code "81") (name "unconnected-(USB4-EP-Pad5)") (class "Default")
      (node (ref "USB4") (pin "5") (pinfunction "EP_5") (pintype "unspecified+no_connect"))
    )
    (net (code "82") (name "unconnected-(USB4-SSRXn1-PadB10)") (class "Default")
      (node (ref "USB4") (pin "B10") (pinfunction "SSRXn1_B10") (pintype "unspecified+no_connect"))
    )
    (net (code "83") (name "unconnected-(USB4-SSRXn2-PadA10)") (class "Default")
      (node (ref "USB4") (pin "A10") (pinfunction "SSRXn2_A10") (pintype "unspecified+no_connect"))
    )
    (net (code "84") (name "unconnected-(USB4-SSRXp1-PadB11)") (class "Default")
      (node (ref "USB4") (pin "B11") (pinfunction "SSRXp1_B11") (pintype "unspecified+no_connect"))
    )
    (net (code "85") (name "unconnected-(USB4-SSRXp2-PadA11)") (class "Default")
      (node (ref "USB4") (pin "A11") (pinfunction "SSRXp2_A11") (pintype "unspecified+no_connect"))
    )
    (net (code "86") (name "unconnected-(USB4-SSTXP1-PadA2)") (class "Default")
      (node (ref "USB4") (pin "A2") (pinfunction "SSTXP1_A2") (pintype "unspecified+no_connect"))
    )
    (net (code "87") (name "unconnected-(USB4-SSTXn1-PadA3)") (class "Default")
      (node (ref "USB4") (pin "A3") (pinfunction "SSTXn1_A3") (pintype "unspecified+no_connect"))
    )
    (net (code "88") (name "unconnected-(USB4-SSTXn2-PadB3)") (class "Default")
      (node (ref "USB4") (pin "B3") (pinfunction "SSTXn2_B3") (pintype "unspecified+no_connect"))
    )
    (net (code "89") (name "unconnected-(USB4-SSTXp2-PadB2)") (class "Default")
      (node (ref "USB4") (pin "B2") (pinfunction "SSTXp2_B2") (pintype "unspecified+no_connect"))
    )
    (net (code "90") (name "unconnected-(USB4-SUB1-PadA8)") (class "Default")
      (node (ref "USB4") (pin "A8") (pinfunction "SUB1_A8") (pintype "unspecified+no_connect"))
    )
    (net (code "91") (name "unconnected-(USB4-SUB2-PadB8)") (class "Default")
      (node (ref "USB4") (pin "B8") (pinfunction "SUB2_B8") (pintype "unspecified+no_connect"))
    )
    (net (code "92") (name "unconnected-(USB5-CC1-PadA5)") (class "Default")
      (node (ref "USB5") (pin "A5") (pinfunction "CC1_A5") (pintype "unspecified+no_connect"))
    )
    (net (code "93") (name "unconnected-(USB5-CC2-PadB5)") (class "Default")
      (node (ref "USB5") (pin "B5") (pinfunction "CC2_B5") (pintype "unspecified+no_connect"))
    )
    (net (code "94") (name "unconnected-(USB5-DN1-PadA7)") (class "Default")
      (node (ref "USB5") (pin "A7") (pinfunction "DN1_A7") (pintype "unspecified+no_connect"))
    )
    (net (code "95") (name "unconnected-(USB5-DN2-PadB7)") (class "Default")
      (node (ref "USB5") (pin "B7") (pinfunction "DN2_B7") (pintype "unspecified+no_connect"))
    )
    (net (code "96") (name "unconnected-(USB5-DP1-PadA6)") (class "Default")
      (node (ref "USB5") (pin "A6") (pinfunction "DP1_A6") (pintype "unspecified+no_connect"))
    )
    (net (code "97") (name "unconnected-(USB5-DP2-PadB6)") (class "Default")
      (node (ref "USB5") (pin "B6") (pinfunction "DP2_B6") (pintype "unspecified+no_connect"))
    )
    (net (code "98") (name "unconnected-(USB5-EP-Pad1)") (class "Default")
      (node (ref "USB5") (pin "1") (pinfunction "EP_1") (pintype "unspecified+no_connect"))
    )
    (net (code "99") (name "unconnected-(USB5-EP-Pad2)") (class "Default")
      (node (ref "USB5") (pin "2") (pinfunction "EP_2") (pintype "unspecified+no_connect"))
    )
    (net (code "100") (name "unconnected-(USB5-EP-Pad3)") (class "Default")
      (node (ref "USB5") (pin "3") (pinfunction "EP_3") (pintype "unspecified+no_connect"))
    )
    (net (code "101") (name "unconnected-(USB5-EP-Pad4)") (class "Default")
      (node (ref "USB5") (pin "4") (pinfunction "EP_4") (pintype "unspecified+no_connect"))
    )
    (net (code "102") (name "unconnected-(USB5-EP-Pad5)") (class "Default")
      (node (ref "USB5") (pin "5") (pinfunction "EP_5") (pintype "unspecified+no_connect"))
    )
    (net (code "103") (name "unconnected-(USB5-SSRXn1-PadB10)") (class "Default")
      (node (ref "USB5") (pin "B10") (pinfunction "SSRXn1_B10") (pintype "unspecified+no_connect"))
    )
    (net (code "104") (name "unconnected-(USB5-SSRXn2-PadA10)") (class "Default")
      (node (ref "USB5") (pin "A10") (pinfunction "SSRXn2_A10") (pintype "unspecified+no_connect"))
    )
    (net (code "105") (name "unconnected-(USB5-SSRXp1-PadB11)") (class "Default")
      (node (ref "USB5") (pin "B11") (pinfunction "SSRXp1_B11") (pintype "unspecified+no_connect"))
    )
    (net (code "106") (name "unconnected-(USB5-SSRXp2-PadA11)") (class "Default")
      (node (ref "USB5") (pin "A11") (pinfunction "SSRXp2_A11") (pintype "unspecified+no_connect"))
    )
    (net (code "107") (name "unconnected-(USB5-SSTXP1-PadA2)") (class "Default")
      (node (ref "USB5") (pin "A2") (pinfunction "SSTXP1_A2") (pintype "unspecified+no_connect"))
    )
    (net (code "108") (name "unconnected-(USB5-SSTXn1-PadA3)") (class "Default")
      (node (ref "USB5") (pin "A3") (pinfunction "SSTXn1_A3") (pintype "unspecified+no_connect"))
    )
    (net (code "109") (name "unconnected-(USB5-SSTXn2-PadB3)") (class "Default")
      (node (ref "USB5") (pin "B3") (pinfunction "SSTXn2_B3") (pintype "unspecified+no_connect"))
    )
    (net (code "110") (name "unconnected-(USB5-SSTXp2-PadB2)") (class "Default")
      (node (ref "USB5") (pin "B2") (pinfunction "SSTXp2_B2") (pintype "unspecified+no_connect"))
    )
    (net (code "111") (name "unconnected-(USB5-SUB1-PadA8)") (class "Default")
      (node (ref "USB5") (pin "A8") (pinfunction "SUB1_A8") (pintype "unspecified+no_connect"))
    )
    (net (code "112") (name "unconnected-(USB5-SUB2-PadB8)") (class "Default")
      (node (ref "USB5") (pin "B8") (pinfunction "SUB2_B8") (pintype "unspecified+no_connect"))
    )
    (net (code "113") (name "unconnected-(USB6-CC1-PadA5)") (class "Default")
      (node (ref "USB6") (pin "A5") (pinfunction "CC1_A5") (pintype "unspecified+no_connect"))
    )
    (net (code "114") (name "unconnected-(USB6-CC2-PadB5)") (class "Default")
      (node (ref "USB6") (pin "B5") (pinfunction "CC2_B5") (pintype "unspecified+no_connect"))
    )
    (net (code "115") (name "unconnected-(USB6-DN1-PadA7)") (class "Default")
      (node (ref "USB6") (pin "A7") (pinfunction "DN1_A7") (pintype "unspecified+no_connect"))
    )
    (net (code "116") (name "unconnected-(USB6-DN2-PadB7)") (class "Default")
      (node (ref "USB6") (pin "B7") (pinfunction "DN2_B7") (pintype "unspecified+no_connect"))
    )
    (net (code "117") (name "unconnected-(USB6-DP1-PadA6)") (class "Default")
      (node (ref "USB6") (pin "A6") (pinfunction "DP1_A6") (pintype "unspecified+no_connect"))
    )
    (net (code "118") (name "unconnected-(USB6-DP2-PadB6)") (class "Default")
      (node (ref "USB6") (pin "B6") (pinfunction "DP2_B6") (pintype "unspecified+no_connect"))
    )
    (net (code "119") (name "unconnected-(USB6-EP-Pad1)") (class "Default")
      (node (ref "USB6") (pin "1") (pinfunction "EP_1") (pintype "unspecified+no_connect"))
    )
    (net (code "120") (name "unconnected-(USB6-EP-Pad2)") (class "Default")
      (node (ref "USB6") (pin "2") (pinfunction "EP_2") (pintype "unspecified+no_connect"))
    )
    (net (code "121") (name "unconnected-(USB6-EP-Pad3)") (class "Default")
      (node (ref "USB6") (pin "3") (pinfunction "EP_3") (pintype "unspecified+no_connect"))
    )
    (net (code "122") (name "unconnected-(USB6-EP-Pad4)") (class "Default")
      (node (ref "USB6") (pin "4") (pinfunction "EP_4") (pintype "unspecified+no_connect"))
    )
    (net (code "123") (name "unconnected-(USB6-EP-Pad5)") (class "Default")
      (node (ref "USB6") (pin "5") (pinfunction "EP_5") (pintype "unspecified+no_connect"))
    )
    (net (code "124") (name "unconnected-(USB6-SSRXn1-PadB10)") (class "Default")
      (node (ref "USB6") (pin "B10") (pinfunction "SSRXn1_B10") (pintype "unspecified+no_connect"))
    )
    (net (code "125") (name "unconnected-(USB6-SSRXn2-PadA10)") (class "Default")
      (node (ref "USB6") (pin "A10") (pinfunction "SSRXn2_A10") (pintype "unspecified+no_connect"))
    )
    (net (code "126") (name "unconnected-(USB6-SSRXp1-PadB11)") (class "Default")
      (node (ref "USB6") (pin "B11") (pinfunction "SSRXp1_B11") (pintype "unspecified+no_connect"))
    )
    (net (code "127") (name "unconnected-(USB6-SSRXp2-PadA11)") (class "Default")
      (node (ref "USB6") (pin "A11") (pinfunction "SSRXp2_A11") (pintype "unspecified+no_connect"))
    )
    (net (code "128") (name "unconnected-(USB6-SSTXP1-PadA2)") (class "Default")
      (node (ref "USB6") (pin "A2") (pinfunction "SSTXP1_A2") (pintype "unspecified+no_connect"))
    )
    (net (code "129") (name "unconnected-(USB6-SSTXn1-PadA3)") (class "Default")
      (node (ref "USB6") (pin "A3") (pinfunction "SSTXn1_A3") (pintype "unspecified+no_connect"))
    )
    (net (code "130") (name "unconnected-(USB6-SSTXn2-PadB3)") (class "Default")
      (node (ref "USB6") (pin "B3") (pinfunction "SSTXn2_B3") (pintype "unspecified+no_connect"))
    )
    (net (code "131") (name "unconnected-(USB6-SSTXp2-PadB2)") (class "Default")
      (node (ref "USB6") (pin "B2") (pinfunction "SSTXp2_B2") (pintype "unspecified+no_connect"))
    )
    (net (code "132") (name "unconnected-(USB6-SUB1-PadA8)") (class "Default")
      (node (ref "USB6") (pin "A8") (pinfunction "SUB1_A8") (pintype "unspecified+no_connect"))
    )
    (net (code "133") (name "unconnected-(USB6-SUB2-PadB8)") (class "Default")
      (node (ref "USB6") (pin "B8") (pinfunction "SUB2_B8") (pintype "unspecified+no_connect"))
    )
    (net (code "134") (name "unconnected-(USB7-CC1-PadA5)") (class "Default")
      (node (ref "USB7") (pin "A5") (pinfunction "CC1_A5") (pintype "unspecified+no_connect"))
    )
    (net (code "135") (name "unconnected-(USB7-CC2-PadB5)") (class "Default")
      (node (ref "USB7") (pin "B5") (pinfunction "CC2_B5") (pintype "unspecified+no_connect"))
    )
    (net (code "136") (name "unconnected-(USB7-DN1-PadA7)") (class "Default")
      (node (ref "USB7") (pin "A7") (pinfunction "DN1_A7") (pintype "unspecified+no_connect"))
    )
    (net (code "137") (name "unconnected-(USB7-DN2-PadB7)") (class "Default")
      (node (ref "USB7") (pin "B7") (pinfunction "DN2_B7") (pintype "unspecified+no_connect"))
    )
    (net (code "138") (name "unconnected-(USB7-DP1-PadA6)") (class "Default")
      (node (ref "USB7") (pin "A6") (pinfunction "DP1_A6") (pintype "unspecified+no_connect"))
    )
    (net (code "139") (name "unconnected-(USB7-DP2-PadB6)") (class "Default")
      (node (ref "USB7") (pin "B6") (pinfunction "DP2_B6") (pintype "unspecified+no_connect"))
    )
    (net (code "140") (name "unconnected-(USB7-EP-Pad1)") (class "Default")
      (node (ref "USB7") (pin "1") (pinfunction "EP_1") (pintype "unspecified+no_connect"))
    )
    (net (code "141") (name "unconnected-(USB7-EP-Pad2)") (class "Default")
      (node (ref "USB7") (pin "2") (pinfunction "EP_2") (pintype "unspecified+no_connect"))
    )
    (net (code "142") (name "unconnected-(USB7-EP-Pad3)") (class "Default")
      (node (ref "USB7") (pin "3") (pinfunction "EP_3") (pintype "unspecified+no_connect"))
    )
    (net (code "143") (name "unconnected-(USB7-EP-Pad4)") (class "Default")
      (node (ref "USB7") (pin "4") (pinfunction "EP_4") (pintype "unspecified+no_connect"))
    )
    (net (code "144") (name "unconnected-(USB7-EP-Pad5)") (class "Default")
      (node (ref "USB7") (pin "5") (pinfunction "EP_5") (pintype "unspecified+no_connect"))
    )
    (net (code "145") (name "unconnected-(USB7-SSRXn1-PadB10)") (class "Default")
      (node (ref "USB7") (pin "B10") (pinfunction "SSRXn1_B10") (pintype "unspecified+no_connect"))
    )
    (net (code "146") (name "unconnected-(USB7-SSRXn2-PadA10)") (class "Default")
      (node (ref "USB7") (pin "A10") (pinfunction "SSRXn2_A10") (pintype "unspecified+no_connect"))
    )
    (net (code "147") (name "unconnected-(USB7-SSRXp1-PadB11)") (class "Default")
      (node (ref "USB7") (pin "B11") (pinfunction "SSRXp1_B11") (pintype "unspecified+no_connect"))
    )
    (net (code "148") (name "unconnected-(USB7-SSRXp2-PadA11)") (class "Default")
      (node (ref "USB7") (pin "A11") (pinfunction "SSRXp2_A11") (pintype "unspecified+no_connect"))
    )
    (net (code "149") (name "unconnected-(USB7-SSTXP1-PadA2)") (class "Default")
      (node (ref "USB7") (pin "A2") (pinfunction "SSTXP1_A2") (pintype "unspecified+no_connect"))
    )
    (net (code "150") (name "unconnected-(USB7-SSTXn1-PadA3)") (class "Default")
      (node (ref "USB7") (pin "A3") (pinfunction "SSTXn1_A3") (pintype "unspecified+no_connect"))
    )
    (net (code "151") (name "unconnected-(USB7-SSTXn2-PadB3)") (class "Default")
      (node (ref "USB7") (pin "B3") (pinfunction "SSTXn2_B3") (pintype "unspecified+no_connect"))
    )
    (net (code "152") (name "unconnected-(USB7-SSTXp2-PadB2)") (class "Default")
      (node (ref "USB7") (pin "B2") (pinfunction "SSTXp2_B2") (pintype "unspecified+no_connect"))
    )
    (net (code "153") (name "unconnected-(USB7-SUB1-PadA8)") (class "Default")
      (node (ref "USB7") (pin "A8") (pinfunction "SUB1_A8") (pintype "unspecified+no_connect"))
    )
    (net (code "154") (name "unconnected-(USB7-SUB2-PadB8)") (class "Default")
      (node (ref "USB7") (pin "B8") (pinfunction "SUB2_B8") (pintype "unspecified+no_connect"))
    )
    (net (code "155") (name "unconnected-(USB8-CC1-PadA5)") (class "Default")
      (node (ref "USB8") (pin "A5") (pinfunction "CC1_A5") (pintype "unspecified+no_connect"))
    )
    (net (code "156") (name "unconnected-(USB8-CC2-PadB5)") (class "Default")
      (node (ref "USB8") (pin "B5") (pinfunction "CC2_B5") (pintype "unspecified+no_connect"))
    )
    (net (code "157") (name "unconnected-(USB8-DN1-PadA7)") (class "Default")
      (node (ref "USB8") (pin "A7") (pinfunction "DN1_A7") (pintype "unspecified+no_connect"))
    )
    (net (code "158") (name "unconnected-(USB8-DN2-PadB7)") (class "Default")
      (node (ref "USB8") (pin "B7") (pinfunction "DN2_B7") (pintype "unspecified+no_connect"))
    )
    (net (code "159") (name "unconnected-(USB8-DP1-PadA6)") (class "Default")
      (node (ref "USB8") (pin "A6") (pinfunction "DP1_A6") (pintype "unspecified+no_connect"))
    )
    (net (code "160") (name "unconnected-(USB8-DP2-PadB6)") (class "Default")
      (node (ref "USB8") (pin "B6") (pinfunction "DP2_B6") (pintype "unspecified+no_connect"))
    )
    (net (code "161") (name "unconnected-(USB8-EP-Pad1)") (class "Default")
      (node (ref "USB8") (pin "1") (pinfunction "EP_1") (pintype "unspecified+no_connect"))
    )
    (net (code "162") (name "unconnected-(USB8-EP-Pad2)") (class "Default")
      (node (ref "USB8") (pin "2") (pinfunction "EP_2") (pintype "unspecified+no_connect"))
    )
    (net (code "163") (name "unconnected-(USB8-EP-Pad3)") (class "Default")
      (node (ref "USB8") (pin "3") (pinfunction "EP_3") (pintype "unspecified+no_connect"))
    )
    (net (code "164") (name "unconnected-(USB8-EP-Pad4)") (class "Default")
      (node (ref "USB8") (pin "4") (pinfunction "EP_4") (pintype "unspecified+no_connect"))
    )
    (net (code "165") (name "unconnected-(USB8-EP-Pad5)") (class "Default")
      (node (ref "USB8") (pin "5") (pinfunction "EP_5") (pintype "unspecified+no_connect"))
    )
    (net (code "166") (name "unconnected-(USB8-SSRXn1-PadB10)") (class "Default")
      (node (ref "USB8") (pin "B10") (pinfunction "SSRXn1_B10") (pintype "unspecified+no_connect"))
    )
    (net (code "167") (name "unconnected-(USB8-SSRXn2-PadA10)") (class "Default")
      (node (ref "USB8") (pin "A10") (pinfunction "SSRXn2_A10") (pintype "unspecified+no_connect"))
    )
    (net (code "168") (name "unconnected-(USB8-SSRXp1-PadB11)") (class "Default")
      (node (ref "USB8") (pin "B11") (pinfunction "SSRXp1_B11") (pintype "unspecified+no_connect"))
    )
    (net (code "169") (name "unconnected-(USB8-SSRXp2-PadA11)") (class "Default")
      (node (ref "USB8") (pin "A11") (pinfunction "SSRXp2_A11") (pintype "unspecified+no_connect"))
    )
    (net (code "170") (name "unconnected-(USB8-SSTXP1-PadA2)") (class "Default")
      (node (ref "USB8") (pin "A2") (pinfunction "SSTXP1_A2") (pintype "unspecified+no_connect"))
    )
    (net (code "171") (name "unconnected-(USB8-SSTXn1-PadA3)") (class "Default")
      (node (ref "USB8") (pin "A3") (pinfunction "SSTXn1_A3") (pintype "unspecified+no_connect"))
    )
    (net (code "172") (name "unconnected-(USB8-SSTXn2-PadB3)") (class "Default")
      (node (ref "USB8") (pin "B3") (pinfunction "SSTXn2_B3") (pintype "unspecified+no_connect"))
    )
    (net (code "173") (name "unconnected-(USB8-SSTXp2-PadB2)") (class "Default")
      (node (ref "USB8") (pin "B2") (pinfunction "SSTXp2_B2") (pintype "unspecified+no_connect"))
    )
    (net (code "174") (name "unconnected-(USB8-SUB1-PadA8)") (class "Default")
      (node (ref "USB8") (pin "A8") (pinfunction "SUB1_A8") (pintype "unspecified+no_connect"))
    )
    (net (code "175") (name "unconnected-(USB8-SUB2-PadB8)") (class "Default")
      (node (ref "USB8") (pin "B8") (pinfunction "SUB2_B8") (pintype "unspecified+no_connect"))
    )
    (net (code "176") (name "unconnected-(USB9-CC1-PadA5)") (class "Default")
      (node (ref "USB9") (pin "A5") (pinfunction "CC1_A5") (pintype "unspecified+no_connect"))
    )
    (net (code "177") (name "unconnected-(USB9-CC2-PadB5)") (class "Default")
      (node (ref "USB9") (pin "B5") (pinfunction "CC2_B5") (pintype "unspecified+no_connect"))
    )
    (net (code "178") (name "unconnected-(USB9-DN1-PadA7)") (class "Default")
      (node (ref "USB9") (pin "A7") (pinfunction "DN1_A7") (pintype "unspecified+no_connect"))
    )
    (net (code "179") (name "unconnected-(USB9-DN2-PadB7)") (class "Default")
      (node (ref "USB9") (pin "B7") (pinfunction "DN2_B7") (pintype "unspecified+no_connect"))
    )
    (net (code "180") (name "unconnected-(USB9-DP1-PadA6)") (class "Default")
      (node (ref "USB9") (pin "A6") (pinfunction "DP1_A6") (pintype "unspecified+no_connect"))
    )
    (net (code "181") (name "unconnected-(USB9-DP2-PadB6)") (class "Default")
      (node (ref "USB9") (pin "B6") (pinfunction "DP2_B6") (pintype "unspecified+no_connect"))
    )
    (net (code "182") (name "unconnected-(USB9-EP-Pad1)") (class "Default")
      (node (ref "USB9") (pin "1") (pinfunction "EP_1") (pintype "unspecified+no_connect"))
    )
    (net (code "183") (name "unconnected-(USB9-EP-Pad2)") (class "Default")
      (node (ref "USB9") (pin "2") (pinfunction "EP_2") (pintype "unspecified+no_connect"))
    )
    (net (code "184") (name "unconnected-(USB9-EP-Pad3)") (class "Default")
      (node (ref "USB9") (pin "3") (pinfunction "EP_3") (pintype "unspecified+no_connect"))
    )
    (net (code "185") (name "unconnected-(USB9-EP-Pad4)") (class "Default")
      (node (ref "USB9") (pin "4") (pinfunction "EP_4") (pintype "unspecified+no_connect"))
    )
    (net (code "186") (name "unconnected-(USB9-EP-Pad5)") (class "Default")
      (node (ref "USB9") (pin "5") (pinfunction "EP_5") (pintype "unspecified+no_connect"))
    )
    (net (code "187") (name "unconnected-(USB9-SSRXn1-PadB10)") (class "Default")
      (node (ref "USB9") (pin "B10") (pinfunction "SSRXn1_B10") (pintype "unspecified+no_connect"))
    )
    (net (code "188") (name "unconnected-(USB9-SSRXn2-PadA10)") (class "Default")
      (node (ref "USB9") (pin "A10") (pinfunction "SSRXn2_A10") (pintype "unspecified+no_connect"))
    )
    (net (code "189") (name "unconnected-(USB9-SSRXp1-PadB11)") (class "Default")
      (node (ref "USB9") (pin "B11") (pinfunction "SSRXp1_B11") (pintype "unspecified+no_connect"))
    )
    (net (code "190") (name "unconnected-(USB9-SSRXp2-PadA11)") (class "Default")
      (node (ref "USB9") (pin "A11") (pinfunction "SSRXp2_A11") (pintype "unspecified+no_connect"))
    )
    (net (code "191") (name "unconnected-(USB9-SSTXP1-PadA2)") (class "Default")
      (node (ref "USB9") (pin "A2") (pinfunction "SSTXP1_A2") (pintype "unspecified+no_connect"))
    )
    (net (code "192") (name "unconnected-(USB9-SSTXn1-PadA3)") (class "Default")
      (node (ref "USB9") (pin "A3") (pinfunction "SSTXn1_A3") (pintype "unspecified+no_connect"))
    )
    (net (code "193") (name "unconnected-(USB9-SSTXn2-PadB3)") (class "Default")
      (node (ref "USB9") (pin "B3") (pinfunction "SSTXn2_B3") (pintype "unspecified+no_connect"))
    )
    (net (code "194") (name "unconnected-(USB9-SSTXp2-PadB2)") (class "Default")
      (node (ref "USB9") (pin "B2") (pinfunction "SSTXp2_B2") (pintype "unspecified+no_connect"))
    )
    (net (code "195") (name "unconnected-(USB9-SUB1-PadA8)") (class "Default")
      (node (ref "USB9") (pin "A8") (pinfunction "SUB1_A8") (pintype "unspecified+no_connect"))
    )
    (net (code "196") (name "unconnected-(USB9-SUB2-PadB8)") (class "Default")
      (node (ref "USB9") (pin "B8") (pinfunction "SUB2_B8") (pintype "unspecified+no_connect"))
    )
    (net (code "197") (name "unconnected-(USB10-CC1-PadA5)") (class "Default")
      (node (ref "USB10") (pin "A5") (pinfunction "CC1_A5") (pintype "unspecified+no_connect"))
    )
    (net (code "198") (name "unconnected-(USB10-CC2-PadB5)") (class "Default")
      (node (ref "USB10") (pin "B5") (pinfunction "CC2_B5") (pintype "unspecified+no_connect"))
    )
    (net (code "199") (name "unconnected-(USB10-DN1-PadA7)") (class "Default")
      (node (ref "USB10") (pin "A7") (pinfunction "DN1_A7") (pintype "unspecified+no_connect"))
    )
    (net (code "200") (name "unconnected-(USB10-DN2-PadB7)") (class "Default")
      (node (ref "USB10") (pin "B7") (pinfunction "DN2_B7") (pintype "unspecified+no_connect"))
    )
    (net (code "201") (name "unconnected-(USB10-DP1-PadA6)") (class "Default")
      (node (ref "USB10") (pin "A6") (pinfunction "DP1_A6") (pintype "unspecified+no_connect"))
    )
    (net (code "202") (name "unconnected-(USB10-DP2-PadB6)") (class "Default")
      (node (ref "USB10") (pin "B6") (pinfunction "DP2_B6") (pintype "unspecified+no_connect"))
    )
    (net (code "203") (name "unconnected-(USB10-EP-Pad1)") (class "Default")
      (node (ref "USB10") (pin "1") (pinfunction "EP_1") (pintype "unspecified+no_connect"))
    )
    (net (code "204") (name "unconnected-(USB10-EP-Pad2)") (class "Default")
      (node (ref "USB10") (pin "2") (pinfunction "EP_2") (pintype "unspecified+no_connect"))
    )
    (net (code "205") (name "unconnected-(USB10-EP-Pad3)") (class "Default")
      (node (ref "USB10") (pin "3") (pinfunction "EP_3") (pintype "unspecified+no_connect"))
    )
    (net (code "206") (name "unconnected-(USB10-EP-Pad4)") (class "Default")
      (node (ref "USB10") (pin "4") (pinfunction "EP_4") (pintype "unspecified+no_connect"))
    )
    (net (code "207") (name "unconnected-(USB10-EP-Pad5)") (class "Default")
      (node (ref "USB10") (pin "5") (pinfunction "EP_5") (pintype "unspecified+no_connect"))
    )
    (net (code "208") (name "unconnected-(USB10-SSRXn1-PadB10)") (class "Default")
      (node (ref "USB10") (pin "B10") (pinfunction "SSRXn1_B10") (pintype "unspecified+no_connect"))
    )
    (net (code "209") (name "unconnected-(USB10-SSRXn2-PadA10)") (class "Default")
      (node (ref "USB10") (pin "A10") (pinfunction "SSRXn2_A10") (pintype "unspecified+no_connect"))
    )
    (net (code "210") (name "unconnected-(USB10-SSRXp1-PadB11)") (class "Default")
      (node (ref "USB10") (pin "B11") (pinfunction "SSRXp1_B11") (pintype "unspecified+no_connect"))
    )
    (net (code "211") (name "unconnected-(USB10-SSRXp2-PadA11)") (class "Default")
      (node (ref "USB10") (pin "A11") (pinfunction "SSRXp2_A11") (pintype "unspecified+no_connect"))
    )
    (net (code "212") (name "unconnected-(USB10-SSTXP1-PadA2)") (class "Default")
      (node (ref "USB10") (pin "A2") (pinfunction "SSTXP1_A2") (pintype "unspecified+no_connect"))
    )
    (net (code "213") (name "unconnected-(USB10-SSTXn1-PadA3)") (class "Default")
      (node (ref "USB10") (pin "A3") (pinfunction "SSTXn1_A3") (pintype "unspecified+no_connect"))
    )
    (net (code "214") (name "unconnected-(USB10-SSTXn2-PadB3)") (class "Default")
      (node (ref "USB10") (pin "B3") (pinfunction "SSTXn2_B3") (pintype "unspecified+no_connect"))
    )
    (net (code "215") (name "unconnected-(USB10-SSTXp2-PadB2)") (class "Default")
      (node (ref "USB10") (pin "B2") (pinfunction "SSTXp2_B2") (pintype "unspecified+no_connect"))
    )
    (net (code "216") (name "unconnected-(USB10-SUB1-PadA8)") (class "Default")
      (node (ref "USB10") (pin "A8") (pinfunction "SUB1_A8") (pintype "unspecified+no_connect"))
    )
    (net (code "217") (name "unconnected-(USB10-SUB2-PadB8)") (class "Default")
      (node (ref "USB10") (pin "B8") (pinfunction "SUB2_B8") (pintype "unspecified+no_connect"))
    )
  )
)
